# PSU_1084SET_3V3.net
KiCad netlist of a schematic drawn in Altium Designer
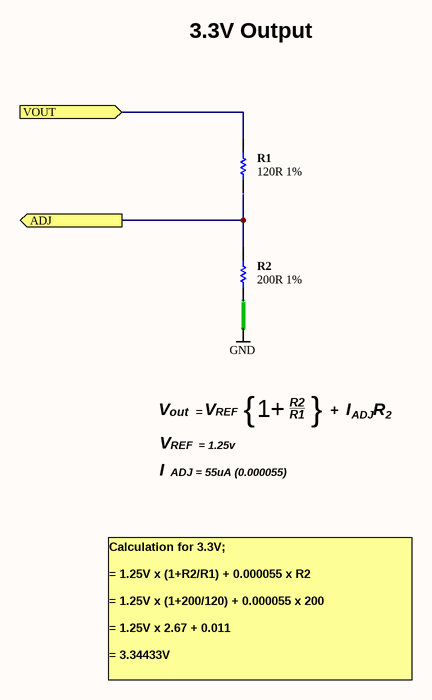
[diagram p0: PSU_1084SET_3V3.SchDoc]

(export (version "E")
  (design (tool "Eeschema 10.0.6"))
  (components
    (comp (ref "R1")
      (value "120R 1%")
      (footprint "RESC1005-STAR")
      (description "Resistor, 120R 1% 0402 (1005)")
      (fields (field (name "TOLERANCE") "1 %"))
      (libsource (lib "AltiumDesignLibrary") (part "RES"))
    )
    (comp (ref "R2")
      (value "200R 1%")
      (footprint "RESC1005-STAR")
      (description "Resistor, 200R 1% 0402 (1005)")
      (fields (field (name "TOLERANCE") "1 %"))
      (libsource (lib "AltiumDesignLibrary") (part "RES"))
    )
  )
  (nets
    (net (code "1") (name "/ADJ") (class "Default")
      (node (ref "R1") (pin "1") (pinfunction "1_1") (pintype "passive"))
      (node (ref "R2") (pin "1") (pinfunction "1_1") (pintype "passive"))
    )
    (net (code "2") (name "/VOUT") (class "Default")
      (node (ref "R1") (pin "2") (pinfunction "2_2") (pintype "passive"))
    )
    (net (code "3") (name "GND") (class "Default")
      (node (ref "R2") (pin "2") (pinfunction "2_2") (pintype "passive"))
    )
  )
)
